# SY80291A8C_5V-3V3-1V2.net
KiCad netlist of a schematic drawn in Altium Designer
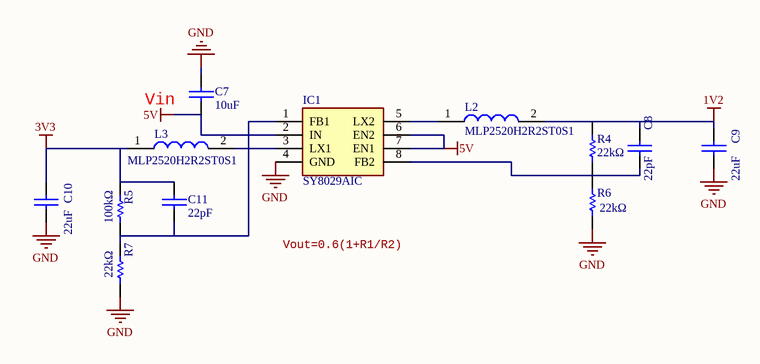
[diagram p0: SY80291A8C 5V-3V3-1V2.SchDoc]

(export (version "E")
  (design (tool "Eeschema 10.0.6"))
  (components
    (comp (ref "C7")
      (value "10uF")
      (footprint "C_0805")
      (description "贴片电容")
      (libsource (lib "IntLib-Passive") (part "Cap_Chip"))
    )
    (comp (ref "C8")
      (value "22pF")
      (footprint "C_0402")
      (description "贴片电容")
      (libsource (lib "IntLib-Passive") (part "Cap_Chip"))
    )
    (comp (ref "C9")
      (value "22uF")
      (footprint "C_0603")
      (description "贴片电容")
      (libsource (lib "IntLib-Passive") (part "Cap_Chip"))
    )
    (comp (ref "C10")
      (value "22uF")
      (footprint "C_0603")
      (description "贴片电容")
      (libsource (lib "IntLib-Passive") (part "Cap_Chip"))
    )
    (comp (ref "C11")
      (value "22pF")
      (footprint "C_0402")
      (description "贴片电容")
      (libsource (lib "IntLib-Passive") (part "Cap_Chip"))
    )
    (comp (ref "IC1")
      (value "SY8029AIC")
      (footprint "SamacSys:SOT65P280X110-8N")
      (description "Integrated Circuit")
      (libsource (lib "*") (part "SY8029AIC"))
    )
    (comp (ref "L2")
      (value "MLP2520H2R2ST0S1")
      (footprint "SamacSys:INDC2520X100N")
      (description "Inductor")
      (fields (field (name "MANUFACTURER_PART_NUMBER") "MLP2520K1R0MT0S1"))
      (libsource (lib "*") (part "MLP2520K1R0MT0S1"))
    )
    (comp (ref "L3")
      (value "MLP2520H2R2ST0S1")
      (footprint "SamacSys:INDC2520X100N")
      (description "Inductor")
      (fields (field (name "MANUFACTURER_PART_NUMBER") "MLP2520K1R0MT0S1"))
      (libsource (lib "*") (part "MLP2520K1R0MT0S1"))
    )
    (comp (ref "R4")
      (value "22kΩ")
      (footprint "R_0402")
      (description "贴片电阻")
      (libsource (lib "IntLib-Passive") (part "Res_Chip"))
    )
    (comp (ref "R5")
      (value "100kΩ")
      (footprint "R_0402")
      (description "贴片电阻")
      (libsource (lib "IntLib-Passive") (part "Res_Chip"))
    )
    (comp (ref "R6")
      (value "22kΩ")
      (footprint "R_0402")
      (description "贴片电阻")
      (libsource (lib "IntLib-Passive") (part "Res_Chip"))
    )
    (comp (ref "R7")
      (value "22kΩ")
      (footprint "R_0402")
      (description "贴片电阻")
      (libsource (lib "IntLib-Passive") (part "Res_Chip"))
    )
  )
  (nets
    (net (code "1") (name "1V2") (class "Default")
      (node (ref "C8") (pin "1") (pinfunction "1_1") (pintype "passive"))
      (node (ref "C9") (pin "1") (pinfunction "1_1") (pintype "passive"))
      (node (ref "L2") (pin "2") (pinfunction "2_2") (pintype "passive"))
      (node (ref "R4") (pin "2") (pinfunction "2_2") (pintype "passive"))
    )
    (net (code "2") (name "3V3") (class "Default")
      (node (ref "C10") (pin "1") (pinfunction "1_1") (pintype "passive"))
      (node (ref "C11") (pin "2") (pinfunction "2_2") (pintype "passive"))
      (node (ref "L3") (pin "1") (pinfunction "1_1") (pintype "passive"))
      (node (ref "R5") (pin "1") (pinfunction "1_1") (pintype "passive"))
    )
    (net (code "3") (name "5V") (class "Default")
      (node (ref "C7") (pin "1") (pinfunction "1_1") (pintype "passive"))
      (node (ref "IC1") (pin "2") (pinfunction "IN_2") (pintype "passive"))
      (node (ref "IC1") (pin "6") (pinfunction "EN2_6") (pintype "passive"))
      (node (ref "IC1") (pin "7") (pinfunction "EN1_7") (pintype "passive"))
    )
    (net (code "4") (name "GND") (class "Default")
      (node (ref "C10") (pin "2") (pinfunction "2_2") (pintype "passive"))
      (node (ref "C7") (pin "2") (pinfunction "2_2") (pintype "passive"))
      (node (ref "C9") (pin "2") (pinfunction "2_2") (pintype "passive"))
      (node (ref "IC1") (pin "4") (pinfunction "GND_4") (pintype "passive"))
      (node (ref "R6") (pin "1") (pinfunction "1_1") (pintype "passive"))
      (node (ref "R7") (pin "2") (pinfunction "2_2") (pintype "passive"))
    )
    (net (code "5") (name "Net-(IC1-FB1)") (class "Default")
      (node (ref "C11") (pin "1") (pinfunction "1_1") (pintype "passive"))
      (node (ref "IC1") (pin "1") (pinfunction "FB1_1") (pintype "passive"))
      (node (ref "R5") (pin "2") (pinfunction "2_2") (pintype "passive"))
      (node (ref "R7") (pin "1") (pinfunction "1_1") (pintype "passive"))
    )
    (net (code "6") (name "Net-(IC1-FB2)") (class "Default")
      (node (ref "C8") (pin "2") (pinfunction "2_2") (pintype "passive"))
      (node (ref "IC1") (pin "8") (pinfunction "FB2_8") (pintype "passive"))
      (node (ref "R4") (pin "1") (pinfunction "1_1") (pintype "passive"))
      (node (ref "R6") (pin "2") (pinfunction "2_2") (pintype "passive"))
    )
    (net (code "7") (name "Net-(IC1-LX1)") (class "Default")
      (node (ref "IC1") (pin "3") (pinfunction "LX1_3") (pintype "passive"))
      (node (ref "L3") (pin "2") (pinfunction "2_2") (pintype "passive"))
    )
    (net (code "8") (name "Net-(IC1-LX2)") (class "Default")
      (node (ref "IC1") (pin "5") (pinfunction "LX2_5") (pintype "passive"))
      (node (ref "L2") (pin "1") (pinfunction "1_1") (pintype "passive"))
    )
  )
)
